# electromechanical-switching-hw.net
KiCad netlist of a schematic drawn in Altium Designer
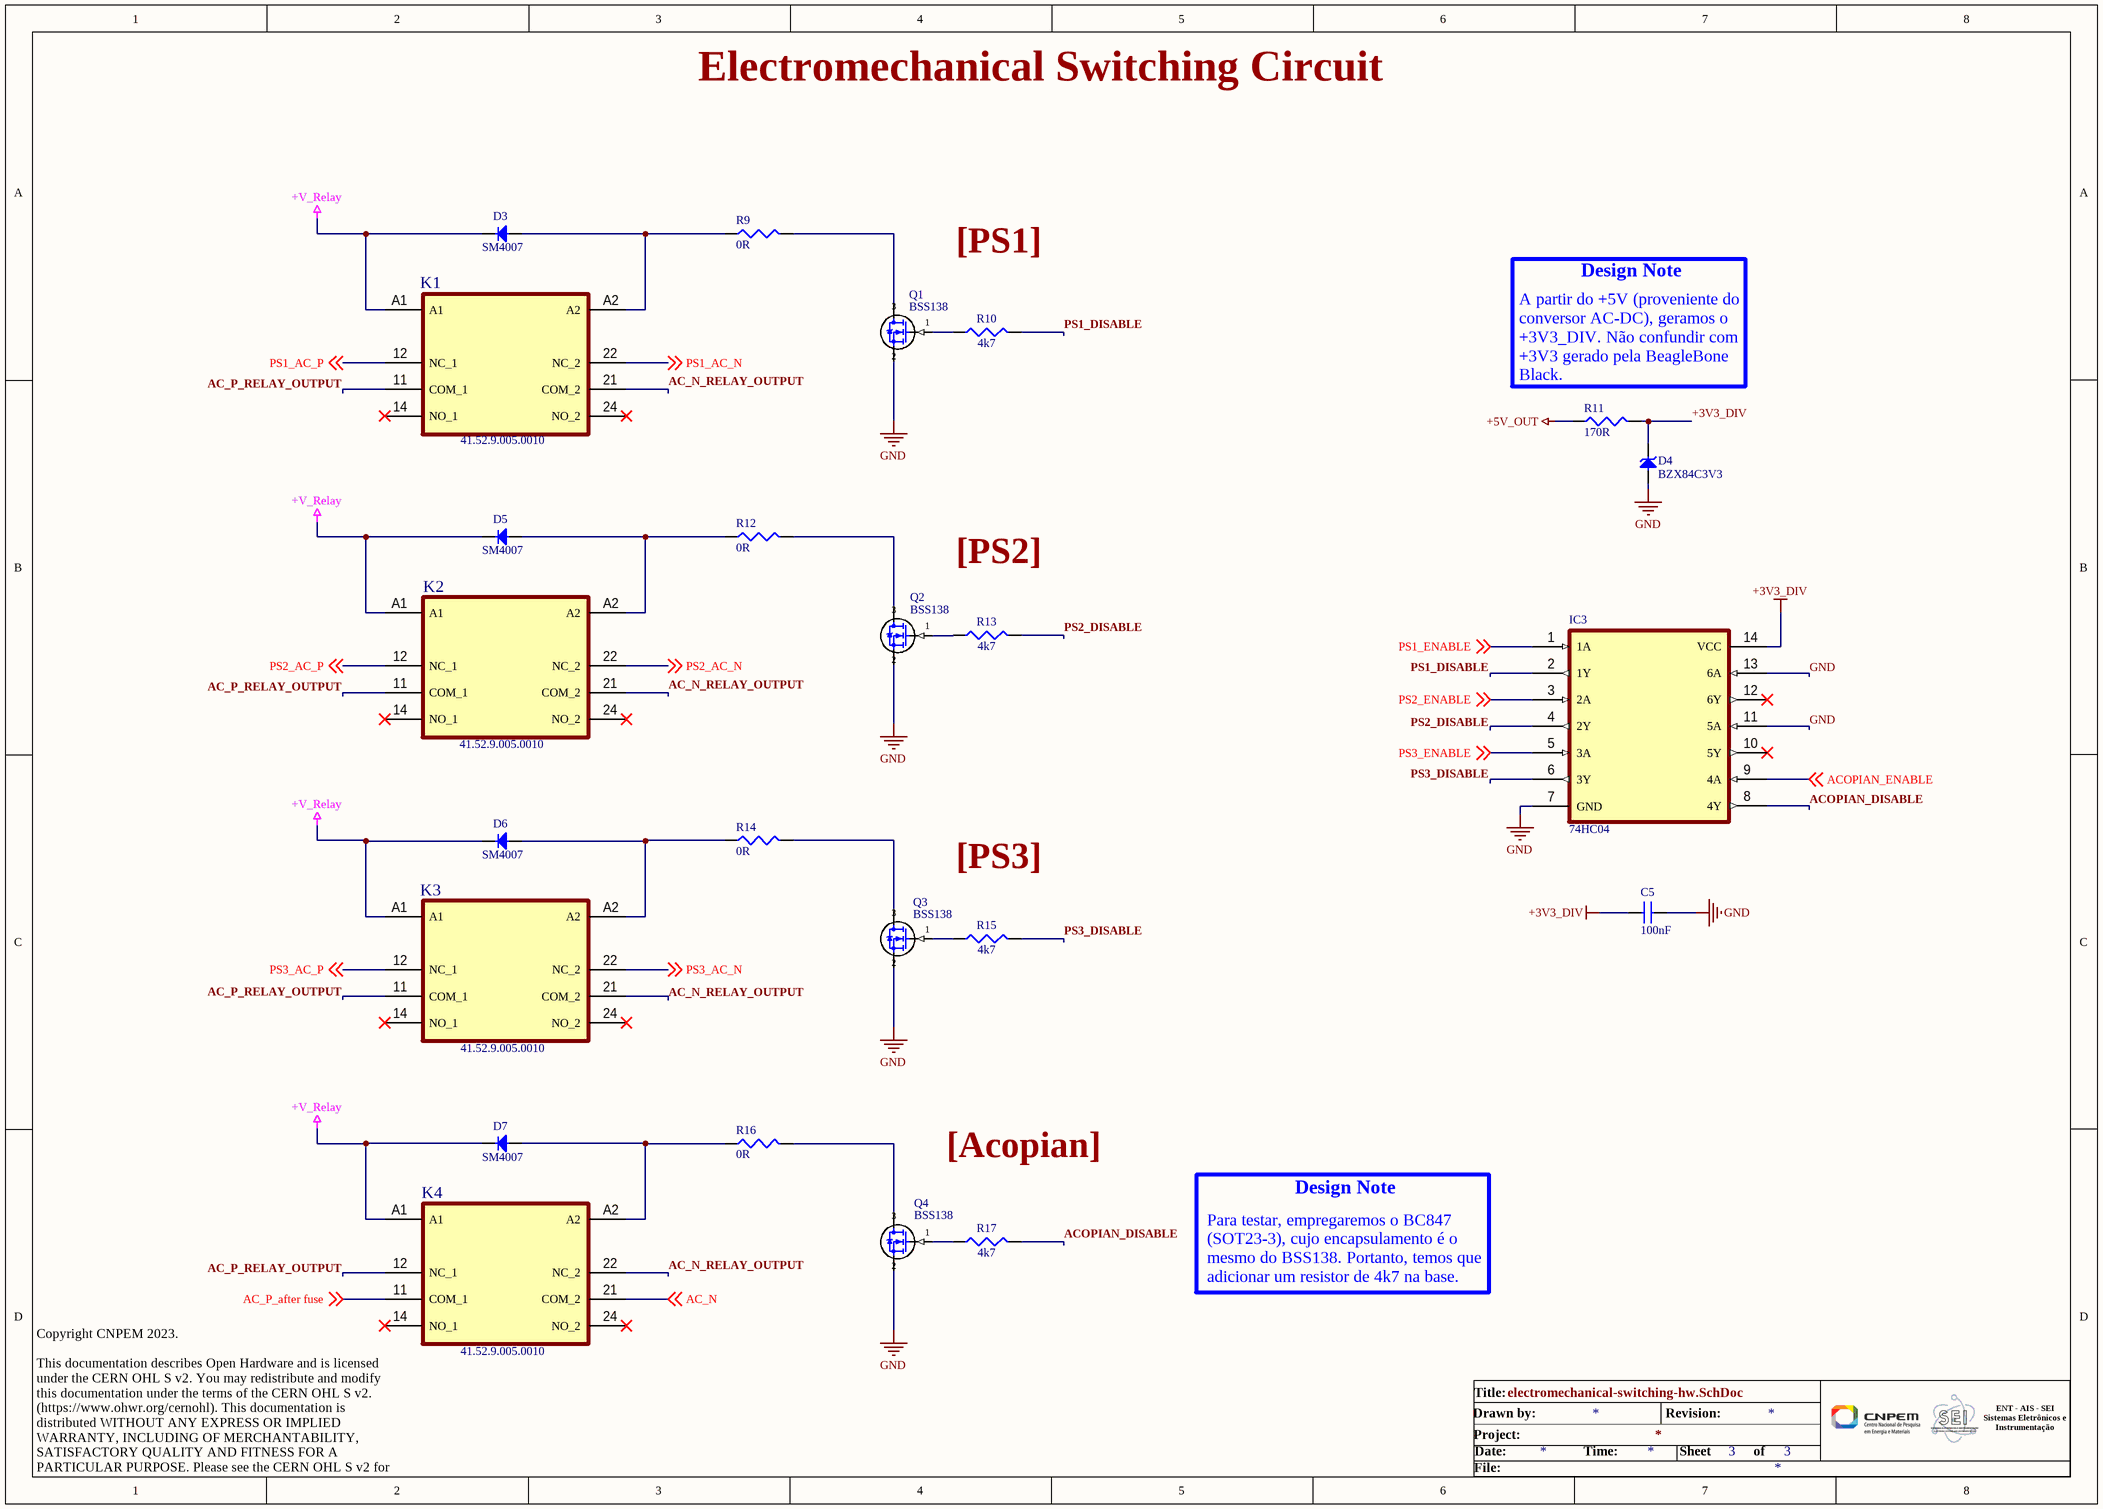
[diagram p0: electromechanical-switching-hw.SchDoc]

(export (version "E")
  (design (tool "Eeschema 10.0.6"))
  (components
    (comp (ref "C5")
      (value "100nF")
      (footprint "C0805")
      (libsource (lib "acopians-powerspy-ac-power-hw-library-schematic") (part "Capacitor 100nF"))
    )
    (comp (ref "D3")
      (value "SM4007")
      (footprint "SM4007")
      (libsource (lib "acopians-powerspy-ac-power-hw-library-schematic") (part "SM4007"))
    )
    (comp (ref "D4")
      (value "BZX84C3V3")
      (footprint "SOT_23_3")
      (description "Zener Diode 3V3")
      (libsource (lib "acopians-powerspy-ac-power-hw-library-schematic") (part "Zener BZX84C3V3"))
    )
    (comp (ref "D5")
      (value "SM4007")
      (footprint "SM4007")
      (libsource (lib "acopians-powerspy-ac-power-hw-library-schematic") (part "SM4007"))
    )
    (comp (ref "D6")
      (value "SM4007")
      (footprint "SM4007")
      (libsource (lib "acopians-powerspy-ac-power-hw-library-schematic") (part "SM4007"))
    )
    (comp (ref "D7")
      (value "SM4007")
      (footprint "SM4007")
      (libsource (lib "acopians-powerspy-ac-power-hw-library-schematic") (part "SM4007"))
    )
    (comp (ref "IC3")
      (value "74HC04")
      (footprint "SOIC-14")
      (description "SOIC14")
      (libsource (lib "acopians-powerspy-ac-power-hw-library-schematic") (part "74HC04 - SOIC14"))
    )
    (comp (ref "K1")
      (value "41.52.9.005.0010")
      (footprint "41.52.9.005.0010")
      (description "Low Profile PCB Relay, 2 CO DPDT, 8A, Coil: 5VDC")
      (libsource (lib "acopians-powerspy-ac-power-hw-library-schematic") (part "41.52.9.005.0010"))
    )
    (comp (ref "K2")
      (value "41.52.9.005.0010")
      (footprint "41.52.9.005.0010")
      (description "Low Profile PCB Relay, 2 CO DPDT, 8A, Coil: 5VDC")
      (libsource (lib "acopians-powerspy-ac-power-hw-library-schematic") (part "41.52.9.005.0010"))
    )
    (comp (ref "K3")
      (value "41.52.9.005.0010")
      (footprint "41.52.9.005.0010")
      (description "Low Profile PCB Relay, 2 CO DPDT, 8A, Coil: 5VDC")
      (libsource (lib "acopians-powerspy-ac-power-hw-library-schematic") (part "41.52.9.005.0010"))
    )
    (comp (ref "K4")
      (value "41.52.9.005.0010")
      (footprint "41.52.9.005.0010")
      (description "Low Profile PCB Relay, 2 CO DPDT, 8A, Coil: 5VDC")
      (libsource (lib "acopians-powerspy-ac-power-hw-library-schematic") (part "41.52.9.005.0010"))
    )
    (comp (ref "Q1")
      (value "BSS138")
      (footprint "SOT_23_3")
      (description "MOSFET N-Channel")
      (libsource (lib "acopians-powerspy-ac-power-hw-library-schematic") (part "BSS138"))
    )
    (comp (ref "Q2")
      (value "BSS138")
      (footprint "SOT_23_3")
      (description "MOSFET N-Channel")
      (libsource (lib "acopians-powerspy-ac-power-hw-library-schematic") (part "BSS138"))
    )
    (comp (ref "Q3")
      (value "BSS138")
      (footprint "SOT_23_3")
      (description "MOSFET N-Channel")
      (libsource (lib "acopians-powerspy-ac-power-hw-library-schematic") (part "BSS138"))
    )
    (comp (ref "Q4")
      (value "BSS138")
      (footprint "SOT_23_3")
      (description "MOSFET N-Channel")
      (libsource (lib "acopians-powerspy-ac-power-hw-library-schematic") (part "BSS138"))
    )
    (comp (ref "R9")
      (value "0R")
      (footprint "R1210")
      (description "Size 1210")
      (libsource (lib "acopians-powerspy-ac-power-hw-library-schematic") (part "Resistor 0R"))
    )
    (comp (ref "R10")
      (value "4k7")
      (footprint "Resistor 0805")
      (description "Size 0805")
      (libsource (lib "acopians-powerspy-ac-power-hw-library-schematic") (part "Resistor 4k7"))
    )
    (comp (ref "R11")
      (value "170R")
      (footprint "R1210")
      (description "Size 1210")
      (libsource (lib "acopians-powerspy-ac-power-hw-library-schematic") (part "Resistor 170R"))
    )
    (comp (ref "R12")
      (value "0R")
      (footprint "R1210")
      (description "Size 1210")
      (libsource (lib "acopians-powerspy-ac-power-hw-library-schematic") (part "Resistor 0R"))
    )
    (comp (ref "R13")
      (value "4k7")
      (footprint "Resistor 0805")
      (description "Size 0805")
      (libsource (lib "acopians-powerspy-ac-power-hw-library-schematic") (part "Resistor 4k7"))
    )
    (comp (ref "R14")
      (value "0R")
      (footprint "R1210")
      (description "Size 1210")
      (libsource (lib "acopians-powerspy-ac-power-hw-library-schematic") (part "Resistor 0R"))
    )
    (comp (ref "R15")
      (value "4k7")
      (footprint "Resistor 0805")
      (description "Size 0805")
      (libsource (lib "acopians-powerspy-ac-power-hw-library-schematic") (part "Resistor 4k7"))
    )
    (comp (ref "R16")
      (value "0R")
      (footprint "R1210")
      (description "Size 1210")
      (libsource (lib "acopians-powerspy-ac-power-hw-library-schematic") (part "Resistor 0R"))
    )
    (comp (ref "R17")
      (value "4k7")
      (footprint "Resistor 0805")
      (description "Size 0805")
      (libsource (lib "acopians-powerspy-ac-power-hw-library-schematic") (part "Resistor 4k7"))
    )
  )
  (nets
    (net (code "1") (name "+3V3_DIV") (class "Default")
      (node (ref "C5") (pin "2") (pinfunction "2_2") (pintype "passive"))
      (node (ref "D4") (pin "3") (pintype "passive"))
      (node (ref "IC3") (pin "14") (pinfunction "VCC_14") (pintype "passive"))
      (node (ref "R11") (pin "2") (pinfunction "2_2") (pintype "passive"))
    )
    (net (code "2") (name "+5V_OUT") (class "Default")
      (node (ref "R11") (pin "1") (pinfunction "1_1") (pintype "passive"))
    )
    (net (code "3") (name "+V_Relay") (class "Default")
      (node (ref "D3") (pin "1") (pintype "passive"))
      (node (ref "D5") (pin "1") (pintype "passive"))
      (node (ref "D6") (pin "1") (pintype "passive"))
      (node (ref "D7") (pin "1") (pintype "passive"))
      (node (ref "K1") (pin "A1") (pinfunction "A1_A1") (pintype "passive"))
      (node (ref "K2") (pin "A1") (pinfunction "A1_A1") (pintype "passive"))
      (node (ref "K3") (pin "A1") (pinfunction "A1_A1") (pintype "passive"))
      (node (ref "K4") (pin "A1") (pinfunction "A1_A1") (pintype "passive"))
    )
    (net (code "4") (name "/ACOPIAN_DISABLE") (class "Default")
      (node (ref "IC3") (pin "8") (pinfunction "4Y_8") (pintype "output"))
      (node (ref "R17") (pin "2") (pinfunction "2_2") (pintype "passive"))
    )
    (net (code "5") (name "/AC_N_RELAY_OUTPUT") (class "Default")
      (node (ref "K1") (pin "21") (pinfunction "COM_2_21") (pintype "passive"))
      (node (ref "K2") (pin "21") (pinfunction "COM_2_21") (pintype "passive"))
      (node (ref "K3") (pin "21") (pinfunction "COM_2_21") (pintype "passive"))
      (node (ref "K4") (pin "22") (pinfunction "NC_2_22") (pintype "passive"))
    )
    (net (code "6") (name "/AC_P_RELAY_OUTPUT") (class "Default")
      (node (ref "K1") (pin "11") (pinfunction "COM_1_11") (pintype "passive"))
      (node (ref "K2") (pin "11") (pinfunction "COM_1_11") (pintype "passive"))
      (node (ref "K3") (pin "11") (pinfunction "COM_1_11") (pintype "passive"))
      (node (ref "K4") (pin "12") (pinfunction "NC_1_12") (pintype "passive"))
    )
    (net (code "7") (name "/PS1_DISABLE") (class "Default")
      (node (ref "IC3") (pin "2") (pinfunction "1Y_2") (pintype "output"))
      (node (ref "R10") (pin "2") (pinfunction "2_2") (pintype "passive"))
    )
    (net (code "8") (name "/PS2_DISABLE") (class "Default")
      (node (ref "IC3") (pin "4") (pinfunction "2Y_4") (pintype "output"))
      (node (ref "R13") (pin "2") (pinfunction "2_2") (pintype "passive"))
    )
    (net (code "9") (name "/PS3_DISABLE") (class "Default")
      (node (ref "IC3") (pin "6") (pinfunction "3Y_6") (pintype "output"))
      (node (ref "R15") (pin "2") (pinfunction "2_2") (pintype "passive"))
    )
    (net (code "10") (name "ACOPIAN_ENABLE") (class "Default")
      (node (ref "IC3") (pin "9") (pinfunction "4A_9") (pintype "input"))
    )
    (net (code "11") (name "AC_N") (class "Default")
      (node (ref "K4") (pin "21") (pinfunction "COM_2_21") (pintype "passive"))
    )
    (net (code "12") (name "AC_P_after fuse") (class "Default")
      (node (ref "K4") (pin "11") (pinfunction "COM_1_11") (pintype "passive"))
    )
    (net (code "13") (name "GND") (class "Default")
      (node (ref "C5") (pin "1") (pinfunction "1_1") (pintype "passive"))
      (node (ref "D4") (pin "1") (pintype "passive"))
      (node (ref "IC3") (pin "11") (pinfunction "5A_11") (pintype "input"))
      (node (ref "IC3") (pin "13") (pinfunction "6A_13") (pintype "input"))
      (node (ref "IC3") (pin "7") (pinfunction "GND_7") (pintype "passive"))
      (node (ref "Q1") (pin "2") (pinfunction "S_2") (pintype "passive"))
      (node (ref "Q2") (pin "2") (pinfunction "S_2") (pintype "passive"))
      (node (ref "Q3") (pin "2") (pinfunction "S_2") (pintype "passive"))
      (node (ref "Q4") (pin "2") (pinfunction "S_2") (pintype "passive"))
    )
    (net (code "14") (name "Net-(D3-Pad2)") (class "Default")
      (node (ref "D3") (pin "2") (pintype "passive"))
      (node (ref "K1") (pin "A2") (pinfunction "A2_A2") (pintype "passive"))
      (node (ref "R9") (pin "1") (pinfunction "1_1") (pintype "passive"))
    )
    (net (code "15") (name "Net-(D5-Pad2)") (class "Default")
      (node (ref "D5") (pin "2") (pintype "passive"))
      (node (ref "K2") (pin "A2") (pinfunction "A2_A2") (pintype "passive"))
      (node (ref "R12") (pin "1") (pinfunction "1_1") (pintype "passive"))
    )
    (net (code "16") (name "Net-(D6-Pad2)") (class "Default")
      (node (ref "D6") (pin "2") (pintype "passive"))
      (node (ref "K3") (pin "A2") (pinfunction "A2_A2") (pintype "passive"))
      (node (ref "R14") (pin "1") (pinfunction "1_1") (pintype "passive"))
    )
    (net (code "17") (name "Net-(D7-Pad2)") (class "Default")
      (node (ref "D7") (pin "2") (pintype "passive"))
      (node (ref "K4") (pin "A2") (pinfunction "A2_A2") (pintype "passive"))
      (node (ref "R16") (pin "1") (pinfunction "1_1") (pintype "passive"))
    )
    (net (code "18") (name "Net-(Q1-D)") (class "Default")
      (node (ref "Q1") (pin "3") (pinfunction "D_3") (pintype "passive"))
      (node (ref "R9") (pin "2") (pinfunction "2_2") (pintype "passive"))
    )
    (net (code "19") (name "Net-(Q1-G)") (class "Default")
      (node (ref "Q1") (pin "1") (pinfunction "G_1") (pintype "input"))
      (node (ref "R10") (pin "1") (pinfunction "1_1") (pintype "passive"))
    )
    (net (code "20") (name "Net-(Q2-D)") (class "Default")
      (node (ref "Q2") (pin "3") (pinfunction "D_3") (pintype "passive"))
      (node (ref "R12") (pin "2") (pinfunction "2_2") (pintype "passive"))
    )
    (net (code "21") (name "Net-(Q2-G)") (class "Default")
      (node (ref "Q2") (pin "1") (pinfunction "G_1") (pintype "input"))
      (node (ref "R13") (pin "1") (pinfunction "1_1") (pintype "passive"))
    )
    (net (code "22") (name "Net-(Q3-D)") (class "Default")
      (node (ref "Q3") (pin "3") (pinfunction "D_3") (pintype "passive"))
      (node (ref "R14") (pin "2") (pinfunction "2_2") (pintype "passive"))
    )
    (net (code "23") (name "Net-(Q3-G)") (class "Default")
      (node (ref "Q3") (pin "1") (pinfunction "G_1") (pintype "input"))
      (node (ref "R15") (pin "1") (pinfunction "1_1") (pintype "passive"))
    )
    (net (code "24") (name "Net-(Q4-D)") (class "Default")
      (node (ref "Q4") (pin "3") (pinfunction "D_3") (pintype "passive"))
      (node (ref "R16") (pin "2") (pinfunction "2_2") (pintype "passive"))
    )
    (net (code "25") (name "Net-(Q4-G)") (class "Default")
      (node (ref "Q4") (pin "1") (pinfunction "G_1") (pintype "input"))
      (node (ref "R17") (pin "1") (pinfunction "1_1") (pintype "passive"))
    )
    (net (code "26") (name "PS1_AC_N") (class "Default")
      (node (ref "K1") (pin "22") (pinfunction "NC_2_22") (pintype "passive"))
    )
    (net (code "27") (name "PS1_AC_P") (class "Default")
      (node (ref "K1") (pin "12") (pinfunction "NC_1_12") (pintype "passive"))
    )
    (net (code "28") (name "PS1_ENABLE") (class "Default")
      (node (ref "IC3") (pin "1") (pinfunction "1A_1") (pintype "input"))
    )
    (net (code "29") (name "PS2_AC_N") (class "Default")
      (node (ref "K2") (pin "22") (pinfunction "NC_2_22") (pintype "passive"))
    )
    (net (code "30") (name "PS2_AC_P") (class "Default")
      (node (ref "K2") (pin "12") (pinfunction "NC_1_12") (pintype "passive"))
    )
    (net (code "31") (name "PS2_ENABLE") (class "Default")
      (node (ref "IC3") (pin "3") (pinfunction "2A_3") (pintype "input"))
    )
    (net (code "32") (name "PS3_AC_N") (class "Default")
      (node (ref "K3") (pin "22") (pinfunction "NC_2_22") (pintype "passive"))
    )
    (net (code "33") (name "PS3_AC_P") (class "Default")
      (node (ref "K3") (pin "12") (pinfunction "NC_1_12") (pintype "passive"))
    )
    (net (code "34") (name "PS3_ENABLE") (class "Default")
      (node (ref "IC3") (pin "5") (pinfunction "3A_5") (pintype "input"))
    )
    (net (code "35") (name "unconnected-(IC3-5Y-Pad10)") (class "Default")
      (node (ref "IC3") (pin "10") (pinfunction "5Y_10") (pintype "output+no_connect"))
    )
    (net (code "36") (name "unconnected-(IC3-6Y-Pad12)") (class "Default")
      (node (ref "IC3") (pin "12") (pinfunction "6Y_12") (pintype "output+no_connect"))
    )
    (net (code "37") (name "unconnected-(K1-NO_1-Pad14)") (class "Default")
      (node (ref "K1") (pin "14") (pinfunction "NO_1_14") (pintype "passive+no_connect"))
    )
    (net (code "38") (name "unconnected-(K1-NO_2-Pad24)") (class "Default")
      (node (ref "K1") (pin "24") (pinfunction "NO_2_24") (pintype "passive+no_connect"))
    )
    (net (code "39") (name "unconnected-(K2-NO_1-Pad14)") (class "Default")
      (node (ref "K2") (pin "14") (pinfunction "NO_1_14") (pintype "passive+no_connect"))
    )
    (net (code "40") (name "unconnected-(K2-NO_2-Pad24)") (class "Default")
      (node (ref "K2") (pin "24") (pinfunction "NO_2_24") (pintype "passive+no_connect"))
    )
    (net (code "41") (name "unconnected-(K3-NO_1-Pad14)") (class "Default")
      (node (ref "K3") (pin "14") (pinfunction "NO_1_14") (pintype "passive+no_connect"))
    )
    (net (code "42") (name "unconnected-(K3-NO_2-Pad24)") (class "Default")
      (node (ref "K3") (pin "24") (pinfunction "NO_2_24") (pintype "passive+no_connect"))
    )
    (net (code "43") (name "unconnected-(K4-NO_1-Pad14)") (class "Default")
      (node (ref "K4") (pin "14") (pinfunction "NO_1_14") (pintype "passive+no_connect"))
    )
    (net (code "44") (name "unconnected-(K4-NO_2-Pad24)") (class "Default")
      (node (ref "K4") (pin "24") (pinfunction "NO_2_24") (pintype "passive+no_connect"))
    )
  )
)
